# 5_GPIOBanks.net
KiCad netlist of a schematic drawn in Altium Designer
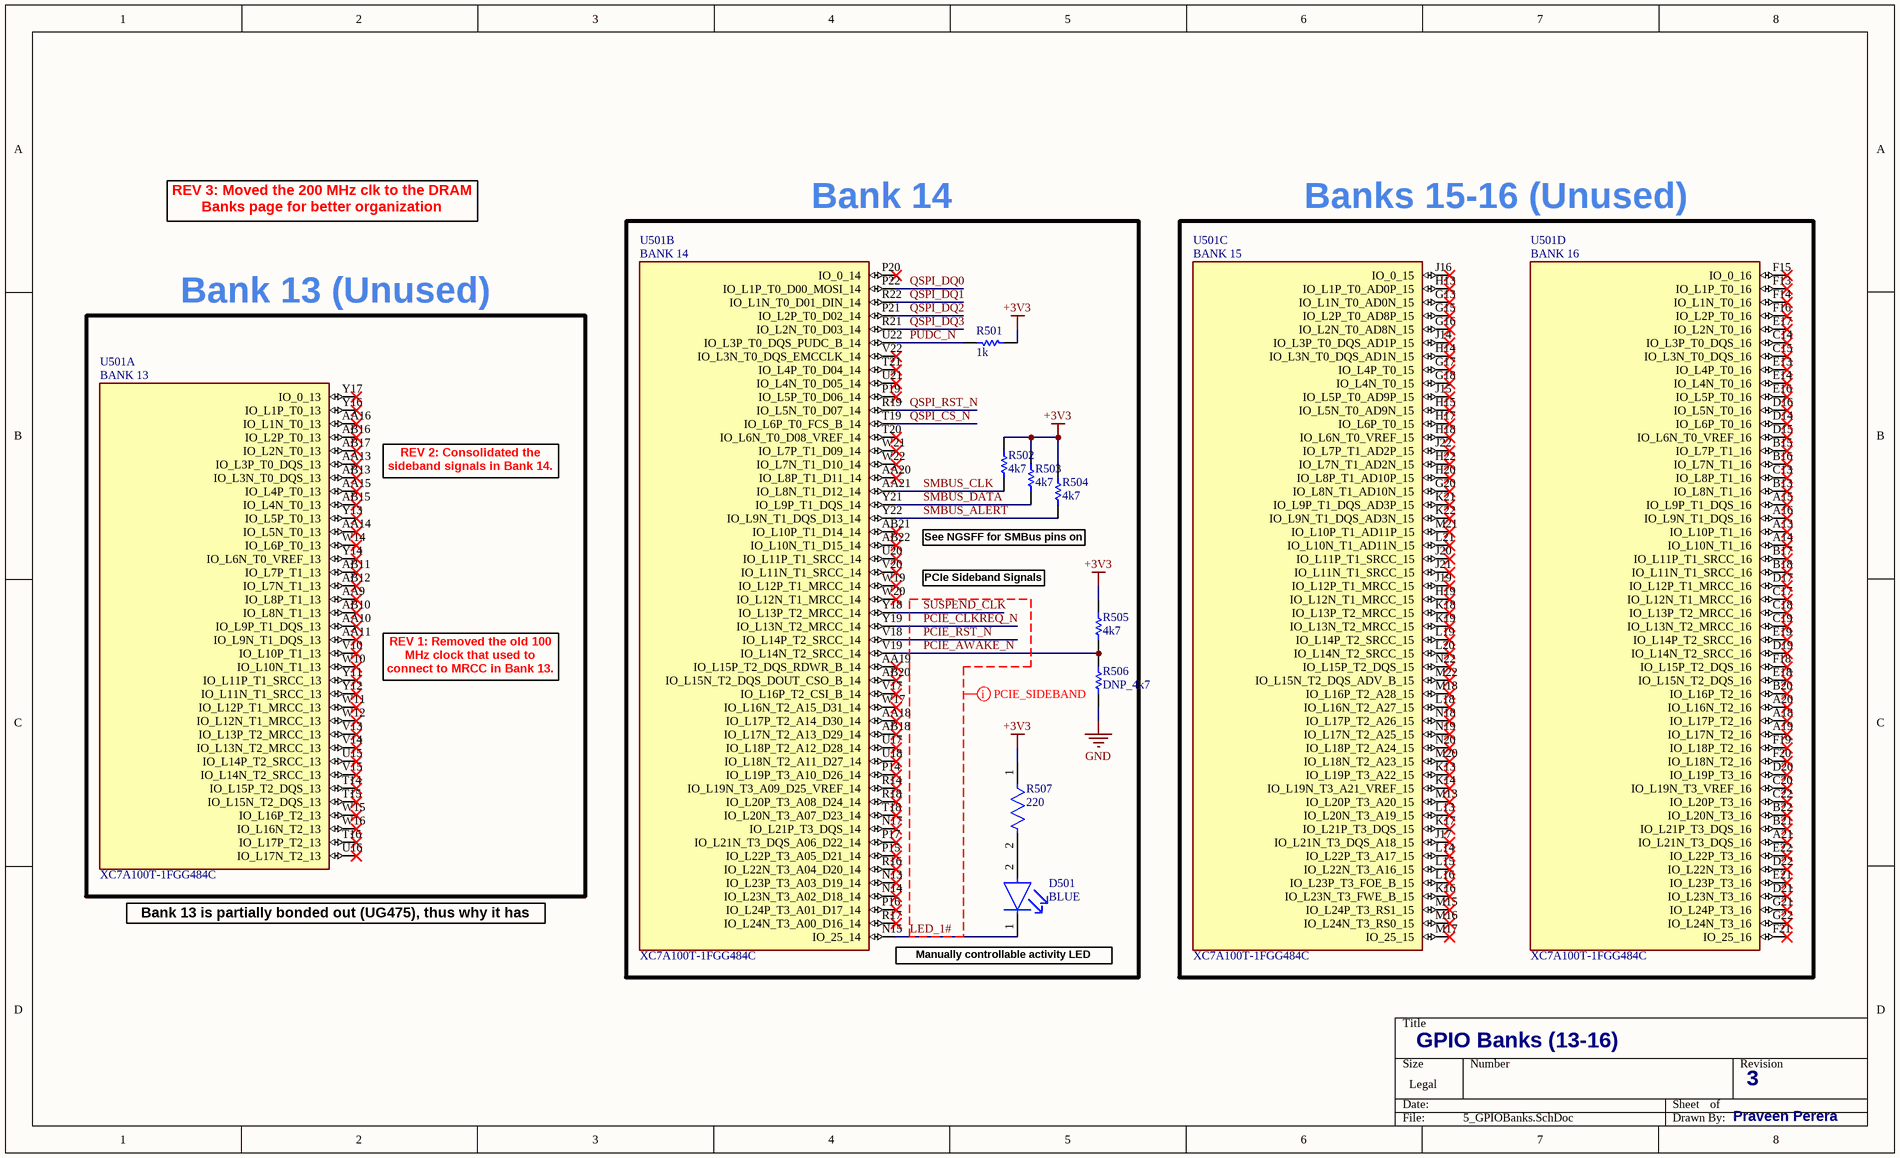
[diagram p0: 5_GPIOBanks.SchDoc]

(export (version "E")
  (design (tool "Eeschema 10.0.6"))
  (components
    (comp (ref "D501")
      (value "BLUE")
      (footprint "FP-LTST-C193TBKT-5A-MFG")
      (description "LTST-C193TBKT-5A\r\n\r\nLED BLUE CLEAR CHIP SMD")
      (libsource (lib "Altium Content Vault") (part "8706943c75ba83719d021d2fdc84c58"))
    )
    (comp (ref "R501")
      (value "1k")
      (footprint "RESC0603X28X15ML05T05")
      (description "CRCW02011K00JNED")
      (fields (field (name "MANUFACTURER") "Vishay Dale"))
      (libsource (lib "Altium Content Vault") (part "RES"))
    )
    (comp (ref "R502")
      (value "4k7")
      (footprint "RESC0603X28X15NL05T05")
      (description "CRCW02014K70FNED")
      (fields (field (name "MANUFACTURER") "Vishay Dale"))
      (libsource (lib "Altium Content Vault") (part "RES"))
    )
    (comp (ref "R503")
      (value "4k7")
      (footprint "RESC0603X28X15NL05T05")
      (description "CRCW02014K70FNED")
      (fields (field (name "MANUFACTURER") "Vishay Dale"))
      (libsource (lib "Altium Content Vault") (part "RES"))
    )
    (comp (ref "R504")
      (value "4k7")
      (footprint "RESC0603X28X15NL05T05")
      (description "CRCW02014K70FNED")
      (fields (field (name "MANUFACTURER") "Vishay Dale"))
      (libsource (lib "Altium Content Vault") (part "RES"))
    )
    (comp (ref "R505")
      (value "4k7")
      (footprint "RESC0603X28X15NL05T05")
      (description "CRCW02014K70FNED")
      (fields (field (name "MANUFACTURER") "Vishay Dale"))
      (libsource (lib "Altium Content Vault") (part "RES"))
    )
    (comp (ref "R506")
      (value "DNP_4k7")
      (footprint "RESC0603X28X15NL05T05")
      (description "CRCW02014K70FNED")
      (fields (field (name "MANUFACTURER") "Vishay Dale"))
      (libsource (lib "Altium Content Vault") (part "RES"))
    )
    (comp (ref "R507")
      (value "220")
      (footprint "FP-CR0402-IPC_B")
      (description "CR0402-FX-2200GLF\r\n\r\nThick Film Chip Resistors 0402 220Ω 0.0625W 1% 100ppm/°C")
      (fields (field (name "TOLERANCE") "1%"))
      (libsource (lib "Altium Content Vault") (part "1029c3af85768c4190bb7ad29bc67b5"))
    )
    (comp (ref "U501")
      (value "XC7A100T-1FGG484C")
      (footprint "BGA484C100P22X22_2300X2300X260N")
      (description "Artix-7 Field Programmable Gate Array (FPGA) IC 285 4976640 101440 484-BBGA")
      (fields (field (name "MF") "Xilinx Inc."))
      (libsource (lib "XC7A100T-1FGG484C - Modified") (part "XC7A100T-1FGG484C"))
    )
  )
  (nets
    (net (code "1") (name "+3V3") (class "Default")
      (node (ref "R501") (pin "1") (pinfunction "1_1") (pintype "passive"))
      (node (ref "R502") (pin "2") (pinfunction "2_2") (pintype "passive"))
      (node (ref "R503") (pin "2") (pinfunction "2_2") (pintype "passive"))
      (node (ref "R504") (pin "2") (pinfunction "2_2") (pintype "passive"))
      (node (ref "R505") (pin "2") (pinfunction "2_2") (pintype "passive"))
      (node (ref "R507") (pin "1") (pinfunction "1_1") (pintype "passive"))
    )
    (net (code "2") (name "/LED_1#") (class "Default")
      (node (ref "D501") (pin "1") (pinfunction "C_1") (pintype "passive"))
      (node (ref "U501") (pin "N15") (pinfunction "IO_25_14_N15") (pintype "bidirectional"))
    )
    (net (code "3") (name "/PCIE_AWAKE_N") (class "Default")
      (node (ref "R505") (pin "1") (pinfunction "1_1") (pintype "passive"))
      (node (ref "R506") (pin "2") (pinfunction "2_2") (pintype "passive"))
      (node (ref "U501") (pin "V19") (pinfunction "IO_L14N_T2_SRCC_14_V19") (pintype "bidirectional"))
    )
    (net (code "4") (name "/PCIE_CLKREQ_N") (class "Default")
      (node (ref "U501") (pin "Y19") (pinfunction "IO_L13N_T2_MRCC_14_Y19") (pintype "bidirectional"))
    )
    (net (code "5") (name "/PCIE_RST_N") (class "Default")
      (node (ref "U501") (pin "V18") (pinfunction "IO_L14P_T2_SRCC_14_V18") (pintype "bidirectional"))
    )
    (net (code "6") (name "/PUDC_N") (class "Default")
      (node (ref "R501") (pin "2") (pinfunction "2_2") (pintype "passive"))
      (node (ref "U501") (pin "U22") (pinfunction "IO_L3P_T0_DQS_PUDC_B_14_U22") (pintype "bidirectional"))
    )
    (net (code "7") (name "/QSPI_CS_N") (class "Default")
      (node (ref "U501") (pin "T19") (pinfunction "IO_L6P_T0_FCS_B_14_T19") (pintype "bidirectional"))
    )
    (net (code "8") (name "/QSPI_DQ0") (class "Default")
      (node (ref "U501") (pin "P22") (pinfunction "IO_L1P_T0_D00_MOSI_14_P22") (pintype "bidirectional"))
    )
    (net (code "9") (name "/QSPI_DQ1") (class "Default")
      (node (ref "U501") (pin "R22") (pinfunction "IO_L1N_T0_D01_DIN_14_R22") (pintype "bidirectional"))
    )
    (net (code "10") (name "/QSPI_DQ2") (class "Default")
      (node (ref "U501") (pin "P21") (pinfunction "IO_L2P_T0_D02_14_P21") (pintype "bidirectional"))
    )
    (net (code "11") (name "/QSPI_DQ3") (class "Default")
      (node (ref "U501") (pin "R21") (pinfunction "IO_L2N_T0_D03_14_R21") (pintype "bidirectional"))
    )
    (net (code "12") (name "/QSPI_RST_N") (class "Default")
      (node (ref "U501") (pin "R19") (pinfunction "IO_L5N_T0_D07_14_R19") (pintype "bidirectional"))
    )
    (net (code "13") (name "/SMBUS_ALERT") (class "Default")
      (node (ref "R504") (pin "1") (pinfunction "1_1") (pintype "passive"))
      (node (ref "U501") (pin "Y22") (pinfunction "IO_L9N_T1_DQS_D13_14_Y22") (pintype "bidirectional"))
    )
    (net (code "14") (name "/SMBUS_CLK") (class "Default")
      (node (ref "R502") (pin "1") (pinfunction "1_1") (pintype "passive"))
      (node (ref "U501") (pin "AA21") (pinfunction "IO_L8N_T1_D12_14_AA21") (pintype "bidirectional"))
    )
    (net (code "15") (name "/SMBUS_DATA") (class "Default")
      (node (ref "R503") (pin "1") (pinfunction "1_1") (pintype "passive"))
      (node (ref "U501") (pin "Y21") (pinfunction "IO_L9P_T1_DQS_14_Y21") (pintype "bidirectional"))
    )
    (net (code "16") (name "/SUSPEND_CLK") (class "Default")
      (node (ref "U501") (pin "Y18") (pinfunction "IO_L13P_T2_MRCC_14_Y18") (pintype "bidirectional"))
    )
    (net (code "17") (name "GND") (class "Default")
      (node (ref "R506") (pin "1") (pinfunction "1_1") (pintype "passive"))
    )
    (net (code "18") (name "Net-(D501-A)") (class "Default")
      (node (ref "D501") (pin "2") (pinfunction "A_2") (pintype "passive"))
      (node (ref "R507") (pin "2") (pinfunction "2_2") (pintype "passive"))
    )
    (net (code "19") (name "unconnected-(U501A-IO_0_13-PadY17)") (class "Default")
      (node (ref "U501") (pin "Y17") (pinfunction "IO_0_13_Y17") (pintype "bidirectional+no_connect"))
    )
    (net (code "20") (name "unconnected-(U501A-IO_L1N_T0_13-PadAA16)") (class "Default")
      (node (ref "U501") (pin "AA16") (pinfunction "IO_L1N_T0_13_AA16") (pintype "bidirectional+no_connect"))
    )
    (net (code "21") (name "unconnected-(U501A-IO_L1P_T0_13-PadY16)") (class "Default")
      (node (ref "U501") (pin "Y16") (pinfunction "IO_L1P_T0_13_Y16") (pintype "bidirectional+no_connect"))
    )
    (net (code "22") (name "unconnected-(U501A-IO_L2N_T0_13-PadAB17)") (class "Default")
      (node (ref "U501") (pin "AB17") (pinfunction "IO_L2N_T0_13_AB17") (pintype "bidirectional+no_connect"))
    )
    (net (code "23") (name "unconnected-(U501A-IO_L2P_T0_13-PadAB16)") (class "Default")
      (node (ref "U501") (pin "AB16") (pinfunction "IO_L2P_T0_13_AB16") (pintype "bidirectional+no_connect"))
    )
    (net (code "24") (name "unconnected-(U501A-IO_L3N_T0_DQS_13-PadAB13)") (class "Default")
      (node (ref "U501") (pin "AB13") (pinfunction "IO_L3N_T0_DQS_13_AB13") (pintype "bidirectional+no_connect"))
    )
    (net (code "25") (name "unconnected-(U501A-IO_L3P_T0_DQS_13-PadAA13)") (class "Default")
      (node (ref "U501") (pin "AA13") (pinfunction "IO_L3P_T0_DQS_13_AA13") (pintype "bidirectional+no_connect"))
    )
    (net (code "26") (name "unconnected-(U501A-IO_L4N_T0_13-PadAB15)") (class "Default")
      (node (ref "U501") (pin "AB15") (pinfunction "IO_L4N_T0_13_AB15") (pintype "bidirectional+no_connect"))
    )
    (net (code "27") (name "unconnected-(U501A-IO_L4P_T0_13-PadAA15)") (class "Default")
      (node (ref "U501") (pin "AA15") (pinfunction "IO_L4P_T0_13_AA15") (pintype "bidirectional+no_connect"))
    )
    (net (code "28") (name "unconnected-(U501A-IO_L5N_T0_13-PadAA14)") (class "Default")
      (node (ref "U501") (pin "AA14") (pinfunction "IO_L5N_T0_13_AA14") (pintype "bidirectional+no_connect"))
    )
    (net (code "29") (name "unconnected-(U501A-IO_L5P_T0_13-PadY13)") (class "Default")
      (node (ref "U501") (pin "Y13") (pinfunction "IO_L5P_T0_13_Y13") (pintype "bidirectional+no_connect"))
    )
    (net (code "30") (name "unconnected-(U501A-IO_L6N_T0_VREF_13-PadY14)") (class "Default")
      (node (ref "U501") (pin "Y14") (pinfunction "IO_L6N_T0_VREF_13_Y14") (pintype "bidirectional+no_connect"))
    )
    (net (code "31") (name "unconnected-(U501A-IO_L6P_T0_13-PadW14)") (class "Default")
      (node (ref "U501") (pin "W14") (pinfunction "IO_L6P_T0_13_W14") (pintype "bidirectional+no_connect"))
    )
    (net (code "32") (name "unconnected-(U501A-IO_L7N_T1_13-PadAB12)") (class "Default")
      (node (ref "U501") (pin "AB12") (pinfunction "IO_L7N_T1_13_AB12") (pintype "bidirectional+no_connect"))
    )
    (net (code "33") (name "unconnected-(U501A-IO_L7P_T1_13-PadAB11)") (class "Default")
      (node (ref "U501") (pin "AB11") (pinfunction "IO_L7P_T1_13_AB11") (pintype "bidirectional+no_connect"))
    )
    (net (code "34") (name "unconnected-(U501A-IO_L8N_T1_13-PadAB10)") (class "Default")
      (node (ref "U501") (pin "AB10") (pinfunction "IO_L8N_T1_13_AB10") (pintype "bidirectional+no_connect"))
    )
    (net (code "35") (name "unconnected-(U501A-IO_L8P_T1_13-PadAA9)") (class "Default")
      (node (ref "U501") (pin "AA9") (pinfunction "IO_L8P_T1_13_AA9") (pintype "bidirectional+no_connect"))
    )
    (net (code "36") (name "unconnected-(U501A-IO_L9N_T1_DQS_13-PadAA11)") (class "Default")
      (node (ref "U501") (pin "AA11") (pinfunction "IO_L9N_T1_DQS_13_AA11") (pintype "bidirectional+no_connect"))
    )
    (net (code "37") (name "unconnected-(U501A-IO_L9P_T1_DQS_13-PadAA10)") (class "Default")
      (node (ref "U501") (pin "AA10") (pinfunction "IO_L9P_T1_DQS_13_AA10") (pintype "bidirectional+no_connect"))
    )
    (net (code "38") (name "unconnected-(U501A-IO_L10N_T1_13-PadW10)") (class "Default")
      (node (ref "U501") (pin "W10") (pinfunction "IO_L10N_T1_13_W10") (pintype "bidirectional+no_connect"))
    )
    (net (code "39") (name "unconnected-(U501A-IO_L10P_T1_13-PadV10)") (class "Default")
      (node (ref "U501") (pin "V10") (pinfunction "IO_L10P_T1_13_V10") (pintype "bidirectional+no_connect"))
    )
    (net (code "40") (name "unconnected-(U501A-IO_L11N_T1_SRCC_13-PadY12)") (class "Default")
      (node (ref "U501") (pin "Y12") (pinfunction "IO_L11N_T1_SRCC_13_Y12") (pintype "bidirectional+no_connect"))
    )
    (net (code "41") (name "unconnected-(U501A-IO_L11P_T1_SRCC_13-PadY11)") (class "Default")
      (node (ref "U501") (pin "Y11") (pinfunction "IO_L11P_T1_SRCC_13_Y11") (pintype "bidirectional+no_connect"))
    )
    (net (code "42") (name "unconnected-(U501A-IO_L12N_T1_MRCC_13-PadW12)") (class "Default")
      (node (ref "U501") (pin "W12") (pinfunction "IO_L12N_T1_MRCC_13_W12") (pintype "bidirectional+no_connect"))
    )
    (net (code "43") (name "unconnected-(U501A-IO_L12P_T1_MRCC_13-PadW11)") (class "Default")
      (node (ref "U501") (pin "W11") (pinfunction "IO_L12P_T1_MRCC_13_W11") (pintype "bidirectional+no_connect"))
    )
    (net (code "44") (name "unconnected-(U501A-IO_L13N_T2_MRCC_13-PadV14)") (class "Default")
      (node (ref "U501") (pin "V14") (pinfunction "IO_L13N_T2_MRCC_13_V14") (pintype "bidirectional+no_connect"))
    )
    (net (code "45") (name "unconnected-(U501A-IO_L13P_T2_MRCC_13-PadV13)") (class "Default")
      (node (ref "U501") (pin "V13") (pinfunction "IO_L13P_T2_MRCC_13_V13") (pintype "bidirectional+no_connect"))
    )
    (net (code "46") (name "unconnected-(U501A-IO_L14N_T2_SRCC_13-PadV15)") (class "Default")
      (node (ref "U501") (pin "V15") (pinfunction "IO_L14N_T2_SRCC_13_V15") (pintype "bidirectional+no_connect"))
    )
    (net (code "47") (name "unconnected-(U501A-IO_L14P_T2_SRCC_13-PadU15)") (class "Default")
      (node (ref "U501") (pin "U15") (pinfunction "IO_L14P_T2_SRCC_13_U15") (pintype "bidirectional+no_connect"))
    )
    (net (code "48") (name "unconnected-(U501A-IO_L15N_T2_DQS_13-PadT15)") (class "Default")
      (node (ref "U501") (pin "T15") (pinfunction "IO_L15N_T2_DQS_13_T15") (pintype "bidirectional+no_connect"))
    )
    (net (code "49") (name "unconnected-(U501A-IO_L15P_T2_DQS_13-PadT14)") (class "Default")
      (node (ref "U501") (pin "T14") (pinfunction "IO_L15P_T2_DQS_13_T14") (pintype "bidirectional+no_connect"))
    )
    (net (code "50") (name "unconnected-(U501A-IO_L16N_T2_13-PadW16)") (class "Default")
      (node (ref "U501") (pin "W16") (pinfunction "IO_L16N_T2_13_W16") (pintype "bidirectional+no_connect"))
    )
    (net (code "51") (name "unconnected-(U501A-IO_L16P_T2_13-PadW15)") (class "Default")
      (node (ref "U501") (pin "W15") (pinfunction "IO_L16P_T2_13_W15") (pintype "bidirectional+no_connect"))
    )
    (net (code "52") (name "unconnected-(U501A-IO_L17N_T2_13-PadU16)") (class "Default")
      (node (ref "U501") (pin "U16") (pinfunction "IO_L17N_T2_13_U16") (pintype "bidirectional+no_connect"))
    )
    (net (code "53") (name "unconnected-(U501A-IO_L17P_T2_13-PadT16)") (class "Default")
      (node (ref "U501") (pin "T16") (pinfunction "IO_L17P_T2_13_T16") (pintype "bidirectional+no_connect"))
    )
    (net (code "54") (name "unconnected-(U501B-IO_0_14-PadP20)") (class "Default")
      (node (ref "U501") (pin "P20") (pinfunction "IO_0_14_P20") (pintype "bidirectional+no_connect"))
    )
    (net (code "55") (name "unconnected-(U501B-IO_L3N_T0_DQS_EMCCLK_14-PadV22)") (class "Default")
      (node (ref "U501") (pin "V22") (pinfunction "IO_L3N_T0_DQS_EMCCLK_14_V22") (pintype "bidirectional+no_connect"))
    )
    (net (code "56") (name "unconnected-(U501B-IO_L4N_T0_D05_14-PadU21)") (class "Default")
      (node (ref "U501") (pin "U21") (pinfunction "IO_L4N_T0_D05_14_U21") (pintype "bidirectional+no_connect"))
    )
    (net (code "57") (name "unconnected-(U501B-IO_L4P_T0_D04_14-PadT21)") (class "Default")
      (node (ref "U501") (pin "T21") (pinfunction "IO_L4P_T0_D04_14_T21") (pintype "bidirectional+no_connect"))
    )
    (net (code "58") (name "unconnected-(U501B-IO_L5P_T0_D06_14-PadP19)") (class "Default")
      (node (ref "U501") (pin "P19") (pinfunction "IO_L5P_T0_D06_14_P19") (pintype "bidirectional+no_connect"))
    )
    (net (code "59") (name "unconnected-(U501B-IO_L6N_T0_D08_VREF_14-PadT20)") (class "Default")
      (node (ref "U501") (pin "T20") (pinfunction "IO_L6N_T0_D08_VREF_14_T20") (pintype "bidirectional+no_connect"))
    )
    (net (code "60") (name "unconnected-(U501B-IO_L7N_T1_D10_14-PadW22)") (class "Default")
      (node (ref "U501") (pin "W22") (pinfunction "IO_L7N_T1_D10_14_W22") (pintype "bidirectional+no_connect"))
    )
    (net (code "61") (name "unconnected-(U501B-IO_L7P_T1_D09_14-PadW21)") (class "Default")
      (node (ref "U501") (pin "W21") (pinfunction "IO_L7P_T1_D09_14_W21") (pintype "bidirectional+no_connect"))
    )
    (net (code "62") (name "unconnected-(U501B-IO_L8P_T1_D11_14-PadAA20)") (class "Default")
      (node (ref "U501") (pin "AA20") (pinfunction "IO_L8P_T1_D11_14_AA20") (pintype "bidirectional+no_connect"))
    )
    (net (code "63") (name "unconnected-(U501B-IO_L10N_T1_D15_14-PadAB22)") (class "Default")
      (node (ref "U501") (pin "AB22") (pinfunction "IO_L10N_T1_D15_14_AB22") (pintype "bidirectional+no_connect"))
    )
    (net (code "64") (name "unconnected-(U501B-IO_L10P_T1_D14_14-PadAB21)") (class "Default")
      (node (ref "U501") (pin "AB21") (pinfunction "IO_L10P_T1_D14_14_AB21") (pintype "bidirectional+no_connect"))
    )
    (net (code "65") (name "unconnected-(U501B-IO_L11N_T1_SRCC_14-PadV20)") (class "Default")
      (node (ref "U501") (pin "V20") (pinfunction "IO_L11N_T1_SRCC_14_V20") (pintype "bidirectional+no_connect"))
    )
    (net (code "66") (name "unconnected-(U501B-IO_L11P_T1_SRCC_14-PadU20)") (class "Default")
      (node (ref "U501") (pin "U20") (pinfunction "IO_L11P_T1_SRCC_14_U20") (pintype "bidirectional+no_connect"))
    )
    (net (code "67") (name "unconnected-(U501B-IO_L12N_T1_MRCC_14-PadW20)") (class "Default")
      (node (ref "U501") (pin "W20") (pinfunction "IO_L12N_T1_MRCC_14_W20") (pintype "bidirectional+no_connect"))
    )
    (net (code "68") (name "unconnected-(U501B-IO_L12P_T1_MRCC_14-PadW19)") (class "Default")
      (node (ref "U501") (pin "W19") (pinfunction "IO_L12P_T1_MRCC_14_W19") (pintype "bidirectional+no_connect"))
    )
    (net (code "69") (name "unconnected-(U501B-IO_L15N_T2_DQS_DOUT_CSO_B_14-PadAB20)") (class "Default")
      (node (ref "U501") (pin "AB20") (pinfunction "IO_L15N_T2_DQS_DOUT_CSO_B_14_AB20") (pintype "bidirectional+no_connect"))
    )
    (net (code "70") (name "unconnected-(U501B-IO_L15P_T2_DQS_RDWR_B_14-PadAA19)") (class "Default")
      (node (ref "U501") (pin "AA19") (pinfunction "IO_L15P_T2_DQS_RDWR_B_14_AA19") (pintype "bidirectional+no_connect"))
    )
    (net (code "71") (name "unconnected-(U501B-IO_L16N_T2_A15_D31_14-PadW17)") (class "Default")
      (node (ref "U501") (pin "W17") (pinfunction "IO_L16N_T2_A15_D31_14_W17") (pintype "bidirectional+no_connect"))
    )
    (net (code "72") (name "unconnected-(U501B-IO_L16P_T2_CSI_B_14-PadV17)") (class "Default")
      (node (ref "U501") (pin "V17") (pinfunction "IO_L16P_T2_CSI_B_14_V17") (pintype "bidirectional+no_connect"))
    )
    (net (code "73") (name "unconnected-(U501B-IO_L17N_T2_A13_D29_14-PadAB18)") (class "Default")
      (node (ref "U501") (pin "AB18") (pinfunction "IO_L17N_T2_A13_D29_14_AB18") (pintype "bidirectional+no_connect"))
    )
    (net (code "74") (name "unconnected-(U501B-IO_L17P_T2_A14_D30_14-PadAA18)") (class "Default")
      (node (ref "U501") (pin "AA18") (pinfunction "IO_L17P_T2_A14_D30_14_AA18") (pintype "bidirectional+no_connect"))
    )
    (net (code "75") (name "unconnected-(U501B-IO_L18N_T2_A11_D27_14-PadU18)") (class "Default")
      (node (ref "U501") (pin "U18") (pinfunction "IO_L18N_T2_A11_D27_14_U18") (pintype "bidirectional+no_connect"))
    )
    (net (code "76") (name "unconnected-(U501B-IO_L18P_T2_A12_D28_14-PadU17)") (class "Default")
      (node (ref "U501") (pin "U17") (pinfunction "IO_L18P_T2_A12_D28_14_U17") (pintype "bidirectional+no_connect"))
    )
    (net (code "77") (name "unconnected-(U501B-IO_L19N_T3_A09_D25_VREF_14-PadR14)") (class "Default")
      (node (ref "U501") (pin "R14") (pinfunction "IO_L19N_T3_A09_D25_VREF_14_R14") (pintype "bidirectional+no_connect"))
    )
    (net (code "78") (name "unconnected-(U501B-IO_L19P_T3_A10_D26_14-PadP14)") (class "Default")
      (node (ref "U501") (pin "P14") (pinfunction "IO_L19P_T3_A10_D26_14_P14") (pintype "bidirectional+no_connect"))
    )
    (net (code "79") (name "unconnected-(U501B-IO_L20N_T3_A07_D23_14-PadT18)") (class "Default")
      (node (ref "U501") (pin "T18") (pinfunction "IO_L20N_T3_A07_D23_14_T18") (pintype "bidirectional+no_connect"))
    )
    (net (code "80") (name "unconnected-(U501B-IO_L20P_T3_A08_D24_14-PadR18)") (class "Default")
      (node (ref "U501") (pin "R18") (pinfunction "IO_L20P_T3_A08_D24_14_R18") (pintype "bidirectional+no_connect"))
    )
    (net (code "81") (name "unconnected-(U501B-IO_L21N_T3_DQS_A06_D22_14-PadP17)") (class "Default")
      (node (ref "U501") (pin "P17") (pinfunction "IO_L21N_T3_DQS_A06_D22_14_P17") (pintype "bidirectional+no_connect"))
    )
    (net (code "82") (name "unconnected-(U501B-IO_L21P_T3_DQS_14-PadN17)") (class "Default")
      (node (ref "U501") (pin "N17") (pinfunction "IO_L21P_T3_DQS_14_N17") (pintype "bidirectional+no_connect"))
    )
    (net (code "83") (name "unconnected-(U501B-IO_L22N_T3_A04_D20_14-PadR16)") (class "Default")
      (node (ref "U501") (pin "R16") (pinfunction "IO_L22N_T3_A04_D20_14_R16") (pintype "bidirectional+no_connect"))
    )
    (net (code "84") (name "unconnected-(U501B-IO_L22P_T3_A05_D21_14-PadP15)") (class "Default")
      (node (ref "U501") (pin "P15") (pinfunction "IO_L22P_T3_A05_D21_14_P15") (pintype "bidirectional+no_connect"))
    )
    (net (code "85") (name "unconnected-(U501B-IO_L23N_T3_A02_D18_14-PadN14)") (class "Default")
      (node (ref "U501") (pin "N14") (pinfunction "IO_L23N_T3_A02_D18_14_N14") (pintype "bidirectional+no_connect"))
    )
    (net (code "86") (name "unconnected-(U501B-IO_L23P_T3_A03_D19_14-PadN13)") (class "Default")
      (node (ref "U501") (pin "N13") (pinfunction "IO_L23P_T3_A03_D19_14_N13") (pintype "bidirectional+no_connect"))
    )
    (net (code "87") (name "unconnected-(U501B-IO_L24N_T3_A00_D16_14-PadR17)") (class "Default")
      (node (ref "U501") (pin "R17") (pinfunction "IO_L24N_T3_A00_D16_14_R17") (pintype "bidirectional+no_connect"))
    )
    (net (code "88") (name "unconnected-(U501B-IO_L24P_T3_A01_D17_14-PadP16)") (class "Default")
      (node (ref "U501") (pin "P16") (pinfunction "IO_L24P_T3_A01_D17_14_P16") (pintype "bidirectional+no_connect"))
    )
    (net (code "89") (name "unconnected-(U501C-IO_0_15-PadJ16)") (class "Default")
      (node (ref "U501") (pin "J16") (pinfunction "IO_0_15_J16") (pintype "bidirectional+no_connect"))
    )
    (net (code "90") (name "unconnected-(U501C-IO_25_15-PadM17)") (class "Default")
      (node (ref "U501") (pin "M17") (pinfunction "IO_25_15_M17") (pintype "bidirectional+no_connect"))
    )
    (net (code "91") (name "unconnected-(U501C-IO_L1N_T0_AD0N_15-PadG13)") (class "Default")
      (node (ref "U501") (pin "G13") (pinfunction "IO_L1N_T0_AD0N_15_G13") (pintype "bidirectional+no_connect"))
    )
    (net (code "92") (name "unconnected-(U501C-IO_L1P_T0_AD0P_15-PadH13)") (class "Default")
      (node (ref "U501") (pin "H13") (pinfunction "IO_L1P_T0_AD0P_15_H13") (pintype "bidirectional+no_connect"))
    )
    (net (code "93") (name "unconnected-(U501C-IO_L2N_T0_AD8N_15-PadG16)") (class "Default")
      (node (ref "U501") (pin "G16") (pinfunction "IO_L2N_T0_AD8N_15_G16") (pintype "bidirectional+no_connect"))
    )
    (net (code "94") (name "unconnected-(U501C-IO_L2P_T0_AD8P_15-PadG15)") (class "Default")
      (node (ref "U501") (pin "G15") (pinfunction "IO_L2P_T0_AD8P_15_G15") (pintype "bidirectional+no_connect"))
    )
    (net (code "95") (name "unconnected-(U501C-IO_L3N_T0_DQS_AD1N_15-PadH14)") (class "Default")
      (node (ref "U501") (pin "H14") (pinfunction "IO_L3N_T0_DQS_AD1N_15_H14") (pintype "bidirectional+no_connect"))
    )
    (net (code "96") (name "unconnected-(U501C-IO_L3P_T0_DQS_AD1P_15-PadJ14)") (class "Default")
      (node (ref "U501") (pin "J14") (pinfunction "IO_L3P_T0_DQS_AD1P_15_J14") (pintype "bidirectional+no_connect"))
    )
    (net (code "97") (name "unconnected-(U501C-IO_L4N_T0_15-PadG18)") (class "Default")
      (node (ref "U501") (pin "G18") (pinfunction "IO_L4N_T0_15_G18") (pintype "bidirectional+no_connect"))
    )
    (net (code "98") (name "unconnected-(U501C-IO_L4P_T0_15-PadG17)") (class "Default")
      (node (ref "U501") (pin "G17") (pinfunction "IO_L4P_T0_15_G17") (pintype "bidirectional+no_connect"))
    )
    (net (code "99") (name "unconnected-(U501C-IO_L5N_T0_AD9N_15-PadH15)") (class "Default")
      (node (ref "U501") (pin "H15") (pinfunction "IO_L5N_T0_AD9N_15_H15") (pintype "bidirectional+no_connect"))
    )
    (net (code "100") (name "unconnected-(U501C-IO_L5P_T0_AD9P_15-PadJ15)") (class "Default")
      (node (ref "U501") (pin "J15") (pinfunction "IO_L5P_T0_AD9P_15_J15") (pintype "bidirectional+no_connect"))
    )
    (net (code "101") (name "unconnected-(U501C-IO_L6N_T0_VREF_15-PadH18)") (class "Default")
      (node (ref "U501") (pin "H18") (pinfunction "IO_L6N_T0_VREF_15_H18") (pintype "bidirectional+no_connect"))
    )
    (net (code "102") (name "unconnected-(U501C-IO_L6P_T0_15-PadH17)") (class "Default")
      (node (ref "U501") (pin "H17") (pinfunction "IO_L6P_T0_15_H17") (pintype "bidirectional+no_connect"))
    )
    (net (code "103") (name "unconnected-(U501C-IO_L7N_T1_AD2N_15-PadH22)") (class "Default")
      (node (ref "U501") (pin "H22") (pinfunction "IO_L7N_T1_AD2N_15_H22") (pintype "bidirectional+no_connect"))
    )
    (net (code "104") (name "unconnected-(U501C-IO_L7P_T1_AD2P_15-PadJ22)") (class "Default")
      (node (ref "U501") (pin "J22") (pinfunction "IO_L7P_T1_AD2P_15_J22") (pintype "bidirectional+no_connect"))
    )
    (net (code "105") (name "unconnected-(U501C-IO_L8N_T1_AD10N_15-PadG20)") (class "Default")
      (node (ref "U501") (pin "G20") (pinfunction "IO_L8N_T1_AD10N_15_G20") (pintype "bidirectional+no_connect"))
    )
    (net (code "106") (name "unconnected-(U501C-IO_L8P_T1_AD10P_15-PadH20)") (class "Default")
      (node (ref "U501") (pin "H20") (pinfunction "IO_L8P_T1_AD10P_15_H20") (pintype "bidirectional+no_connect"))
    )
    (net (code "107") (name "unconnected-(U501C-IO_L9N_T1_DQS_AD3N_15-PadK22)") (class "Default")
      (node (ref "U501") (pin "K22") (pinfunction "IO_L9N_T1_DQS_AD3N_15_K22") (pintype "bidirectional+no_connect"))
    )
    (net (code "108") (name "unconnected-(U501C-IO_L9P_T1_DQS_AD3P_15-PadK21)") (class "Default")
      (node (ref "U501") (pin "K21") (pinfunction "IO_L9P_T1_DQS_AD3P_15_K21") (pintype "bidirectional+no_connect"))
    )
    (net (code "109") (name "unconnected-(U501C-IO_L10N_T1_AD11N_15-PadL21)") (class "Default")
      (node (ref "U501") (pin "L21") (pinfunction "IO_L10N_T1_AD11N_15_L21") (pintype "bidirectional+no_connect"))
    )
    (net (code "110") (name "unconnected-(U501C-IO_L10P_T1_AD11P_15-PadM21)") (class "Default")
      (node (ref "U501") (pin "M21") (pinfunction "IO_L10P_T1_AD11P_15_M21") (pintype "bidirectional+no_connect"))
    )
    (net (code "111") (name "unconnected-(U501C-IO_L11N_T1_SRCC_15-PadJ21)") (class "Default")
      (node (ref "U501") (pin "J21") (pinfunction "IO_L11N_T1_SRCC_15_J21") (pintype "bidirectional+no_connect"))
    )
    (net (code "112") (name "unconnected-(U501C-IO_L11P_T1_SRCC_15-PadJ20)") (class "Default")
      (node (ref "U501") (pin "J20") (pinfunction "IO_L11P_T1_SRCC_15_J20") (pintype "bidirectional+no_connect"))
    )
    (net (code "113") (name "unconnected-(U501C-IO_L12N_T1_MRCC_15-PadH19)") (class "Default")
      (node (ref "U501") (pin "H19") (pinfunction "IO_L12N_T1_MRCC_15_H19") (pintype "bidirectional+no_connect"))
    )
    (net (code "114") (name "unconnected-(U501C-IO_L12P_T1_MRCC_15-PadJ19)") (class "Default")
      (node (ref "U501") (pin "J19") (pinfunction "IO_L12P_T1_MRCC_15_J19") (pintype "bidirectional+no_connect"))
    )
    (net (code "115") (name "unconnected-(U501C-IO_L13N_T2_MRCC_15-PadK19)") (class "Default")
      (node (ref "U501") (pin "K19") (pinfunction "IO_L13N_T2_MRCC_15_K19") (pintype "bidirectional+no_connect"))
    )
    (net (code "116") (name "unconnected-(U501C-IO_L13P_T2_MRCC_15-PadK18)") (class "Default")
      (node (ref "U501") (pin "K18") (pinfunction "IO_L13P_T2_MRCC_15_K18") (pintype "bidirectional+no_connect"))
    )
    (net (code "117") (name "unconnected-(U501C-IO_L14N_T2_SRCC_15-PadL20)") (class "Default")
      (node (ref "U501") (pin "L20") (pinfunction "IO_L14N_T2_SRCC_15_L20") (pintype "bidirectional+no_connect"))
    )
    (net (code "118") (name "unconnected-(U501C-IO_L14P_T2_SRCC_15-PadL19)") (class "Default")
      (node (ref "U501") (pin "L19") (pinfunction "IO_L14P_T2_SRCC_15_L19") (pintype "bidirectional+no_connect"))
    )
    (net (code "119") (name "unconnected-(U501C-IO_L15N_T2_DQS_ADV_B_15-PadM22)") (class "Default")
      (node (ref "U501") (pin "M22") (pinfunction "IO_L15N_T2_DQS_ADV_B_15_M22") (pintype "bidirectional+no_connect"))
    )
    (net (code "120") (name "unconnected-(U501C-IO_L15P_T2_DQS_15-PadN22)") (class "Default")
      (node (ref "U501") (pin "N22") (pinfunction "IO_L15P_T2_DQS_15_N22") (pintype "bidirectional+no_connect"))
    )
    (net (code "121") (name "unconnected-(U501C-IO_L16N_T2_A27_15-PadL18)") (class "Default")
      (node (ref "U501") (pin "L18") (pinfunction "IO_L16N_T2_A27_15_L18") (pintype "bidirectional+no_connect"))
    )
    (net (code "122") (name "unconnected-(U501C-IO_L16P_T2_A28_15-PadM18)") (class "Default")
      (node (ref "U501") (pin "M18") (pinfunction "IO_L16P_T2_A28_15_M18") (pintype "bidirectional+no_connect"))
    )
    (net (code "123") (name "unconnected-(U501C-IO_L17N_T2_A25_15-PadN19)") (class "Default")
      (node (ref "U501") (pin "N19") (pinfunction "IO_L17N_T2_A25_15_N19") (pintype "bidirectional+no_connect"))
    )
    (net (code "124") (name "unconnected-(U501C-IO_L17P_T2_A26_15-PadN18)") (class "Default")
      (node (ref "U501") (pin "N18") (pinfunction "IO_L17P_T2_A26_15_N18") (pintype "bidirectional+no_connect"))
    )
    (net (code "125") (name "unconnected-(U501C-IO_L18N_T2_A23_15-PadM20)") (class "Default")
      (node (ref "U501") (pin "M20") (pinfunction "IO_L18N_T2_A23_15_M20") (pintype "bidirectional+no_connect"))
    )
    (net (code "126") (name "unconnected-(U501C-IO_L18P_T2_A24_15-PadN20)") (class "Default")
      (node (ref "U501") (pin "N20") (pinfunction "IO_L18P_T2_A24_15_N20") (pintype "bidirectional+no_connect"))
    )
    (net (code "127") (name "unconnected-(U501C-IO_L19N_T3_A21_VREF_15-PadK14)") (class "Default")
      (node (ref "U501") (pin "K14") (pinfunction "IO_L19N_T3_A21_VREF_15_K14") (pintype "bidirectional+no_connect"))
    )
    (net (code "128") (name "unconnected-(U501C-IO_L19P_T3_A22_15-PadK13)") (class "Default")
      (node (ref "U501") (pin "K13") (pinfunction "IO_L19P_T3_A22_15_K13") (pintype "bidirectional+no_connect"))
    )
    (net (code "129") (name "unconnected-(U501C-IO_L20N_T3_A19_15-PadL13)") (class "Default")
      (node (ref "U501") (pin "L13") (pinfunction "IO_L20N_T3_A19_15_L13") (pintype "bidirectional+no_connect"))
    )
    (net (code "130") (name "unconnected-(U501C-IO_L20P_T3_A20_15-PadM13)") (class "Default")
      (node (ref "U501") (pin "M13") (pinfunction "IO_L20P_T3_A20_15_M13") (pintype "bidirectional+no_connect"))
    )
    (net (code "131") (name "unconnected-(U501C-IO_L21N_T3_DQS_A18_15-PadJ17)") (class "Default")
      (node (ref "U501") (pin "J17") (pinfunction "IO_L21N_T3_DQS_A18_15_J17") (pintype "bidirectional+no_connect"))
    )
    (net (code "132") (name "unconnected-(U501C-IO_L21P_T3_DQS_15-PadK17)") (class "Default")
      (node (ref "U501") (pin "K17") (pinfunction "IO_L21P_T3_DQS_15_K17") (pintype "bidirectional+no_connect"))
    )
    (net (code "133") (name "unconnected-(U501C-IO_L22N_T3_A16_15-PadL15)") (class "Default")
      (node (ref "U501") (pin "L15") (pinfunction "IO_L22N_T3_A16_15_L15") (pintype "bidirectional+no_connect"))
    )
    (net (code "134") (name "unconnected-(U501C-IO_L22P_T3_A17_15-PadL14)") (class "Default")
      (node (ref "U501") (pin "L14") (pinfunction "IO_L22P_T3_A17_15_L14") (pintype "bidirectional+no_connect"))
    )
    (net (code "135") (name "unconnected-(U501C-IO_L23N_T3_FWE_B_15-PadK16)") (class "Default")
      (node (ref "U501") (pin "K16") (pinfunction "IO_L23N_T3_FWE_B_15_K16") (pintype "bidirectional+no_connect"))
    )
    (net (code "136") (name "unconnected-(U501C-IO_L23P_T3_FOE_B_15-PadL16)") (class "Default")
      (node (ref "U501") (pin "L16") (pinfunction "IO_L23P_T3_FOE_B_15_L16") (pintype "bidirectional+no_connect"))
    )
    (net (code "137") (name "unconnected-(U501C-IO_L24N_T3_RS0_15-PadM16)") (class "Default")
      (node (ref "U501") (pin "M16") (pinfunction "IO_L24N_T3_RS0_15_M16") (pintype "bidirectional+no_connect"))
    )
    (net (code "138") (name "unconnected-(U501C-IO_L24P_T3_RS1_15-PadM15)") (class "Default")
      (node (ref "U501") (pin "M15") (pinfunction "IO_L24P_T3_RS1_15_M15") (pintype "bidirectional+no_connect"))
    )
    (net (code "139") (name "unconnected-(U501D-IO_0_16-PadF15)") (class "Default")
      (node (ref "U501") (pin "F15") (pinfunction "IO_0_16_F15") (pintype "bidirectional+no_connect"))
    )
    (net (code "140") (name "unconnected-(U501D-IO_25_16-PadF21)") (class "Default")
      (node (ref "U501") (pin "F21") (pinfunction "IO_25_16_F21") (pintype "bidirectional+no_connect"))
    )
    (net (code "141") (name "unconnected-(U501D-IO_L1N_T0_16-PadF14)") (class "Default")
      (node (ref "U501") (pin "F14") (pinfunction "IO_L1N_T0_16_F14") (pintype "bidirectional+no_connect"))
    )
    (net (code "142") (name "unconnected-(U501D-IO_L1P_T0_16-PadF13)") (class "Default")
      (node (ref "U501") (pin "F13") (pinfunction "IO_L1P_T0_16_F13") (pintype "bidirectional+no_connect"))
    )
    (net (code "143") (name "unconnected-(U501D-IO_L2N_T0_16-PadE17)") (class "Default")
      (node (ref "U501") (pin "E17") (pinfunction "IO_L2N_T0_16_E17") (pintype "bidirectional+no_connect"))
    )
    (net (code "144") (name "unconnected-(U501D-IO_L2P_T0_16-PadF16)") (class "Default")
      (node (ref "U501") (pin "F16") (pinfunction "IO_L2P_T0_16_F16") (pintype "bidirectional+no_connect"))
    )
    (net (code "145") (name "unconnected-(U501D-IO_L3N_T0_DQS_16-PadC15)") (class "Default")
      (node (ref "U501") (pin "C15") (pinfunction "IO_L3N_T0_DQS_16_C15") (pintype "bidirectional+no_connect"))
    )
    (net (code "146") (name "unconnected-(U501D-IO_L3P_T0_DQS_16-PadC14)") (class "Default")
      (node (ref "U501") (pin "C14") (pinfunction "IO_L3P_T0_DQS_16_C14") (pintype "bidirectional+no_connect"))
    )
    (net (code "147") (name "unconnected-(U501D-IO_L4N_T0_16-PadE14)") (class "Default")
      (node (ref "U501") (pin "E14") (pinfunction "IO_L4N_T0_16_E14") (pintype "bidirectional+no_connect"))
    )
    (net (code "148") (name "unconnected-(U501D-IO_L4P_T0_16-PadE13)") (class "Default")
      (node (ref "U501") (pin "E13") (pinfunction "IO_L4P_T0_16_E13") (pintype "bidirectional+no_connect"))
    )
    (net (code "149") (name "unconnected-(U501D-IO_L5N_T0_16-PadD16)") (class "Default")
      (node (ref "U501") (pin "D16") (pinfunction "IO_L5N_T0_16_D16") (pintype "bidirectional+no_connect"))
    )
    (net (code "150") (name "unconnected-(U501D-IO_L5P_T0_16-PadE16)") (class "Default")
      (node (ref "U501") (pin "E16") (pinfunction "IO_L5P_T0_16_E16") (pintype "bidirectional+no_connect"))
    )
    (net (code "151") (name "unconnected-(U501D-IO_L6N_T0_VREF_16-PadD15)") (class "Default")
      (node (ref "U501") (pin "D15") (pinfunction "IO_L6N_T0_VREF_16_D15") (pintype "bidirectional+no_connect"))
    )
    (net (code "152") (name "unconnected-(U501D-IO_L6P_T0_16-PadD14)") (class "Default")
      (node (ref "U501") (pin "D14") (pinfunction "IO_L6P_T0_16_D14") (pintype "bidirectional+no_connect"))
    )
    (net (code "153") (name "unconnected-(U501D-IO_L7N_T1_16-PadB16)") (class "Default")
      (node (ref "U501") (pin "B16") (pinfunction "IO_L7N_T1_16_B16") (pintype "bidirectional+no_connect"))
    )
    (net (code "154") (name "unconnected-(U501D-IO_L7P_T1_16-PadB15)") (class "Default")
      (node (ref "U501") (pin "B15") (pinfunction "IO_L7P_T1_16_B15") (pintype "bidirectional+no_connect"))
    )
    (net (code "155") (name "unconnected-(U501D-IO_L8N_T1_16-PadB13)") (class "Default")
      (node (ref "U501") (pin "B13") (pinfunction "IO_L8N_T1_16_B13") (pintype "bidirectional+no_connect"))
    )
    (net (code "156") (name "unconnected-(U501D-IO_L8P_T1_16-PadC13)") (class "Default")
      (node (ref "U501") (pin "C13") (pinfunction "IO_L8P_T1_16_C13") (pintype "bidirectional+no_connect"))
    )
    (net (code "157") (name "unconnected-(U501D-IO_L9N_T1_DQS_16-PadA16)") (class "Default")
      (node (ref "U501") (pin "A16") (pinfunction "IO_L9N_T1_DQS_16_A16") (pintype "bidirectional+no_connect"))
    )
    (net (code "158") (name "unconnected-(U501D-IO_L9P_T1_DQS_16-PadA15)") (class "Default")
      (node (ref "U501") (pin "A15") (pinfunction "IO_L9P_T1_DQS_16_A15") (pintype "bidirectional+no_connect"))
    )
    (net (code "159") (name "unconnected-(U501D-IO_L10N_T1_16-PadA14)") (class "Default")
      (node (ref "U501") (pin "A14") (pinfunction "IO_L10N_T1_16_A14") (pintype "bidirectional+no_connect"))
    )
    (net (code "160") (name "unconnected-(U501D-IO_L10P_T1_16-PadA13)") (class "Default")
      (node (ref "U501") (pin "A13") (pinfunction "IO_L10P_T1_16_A13") (pintype "bidirectional+no_connect"))
    )
    (net (code "161") (name "unconnected-(U501D-IO_L11N_T1_SRCC_16-PadB18)") (class "Default")
      (node (ref "U501") (pin "B18") (pinfunction "IO_L11N_T1_SRCC_16_B18") (pintype "bidirectional+no_connect"))
    )
    (net (code "162") (name "unconnected-(U501D-IO_L11P_T1_SRCC_16-PadB17)") (class "Default")
      (node (ref "U501") (pin "B17") (pinfunction "IO_L11P_T1_SRCC_16_B17") (pintype "bidirectional+no_connect"))
    )
    (net (code "163") (name "unconnected-(U501D-IO_L12N_T1_MRCC_16-PadC17)") (class "Default")
      (node (ref "U501") (pin "C17") (pinfunction "IO_L12N_T1_MRCC_16_C17") (pintype "bidirectional+no_connect"))
    )
    (net (code "164") (name "unconnected-(U501D-IO_L12P_T1_MRCC_16-PadD17)") (class "Default")
      (node (ref "U501") (pin "D17") (pinfunction "IO_L12P_T1_MRCC_16_D17") (pintype "bidirectional+no_connect"))
    )
    (net (code "165") (name "unconnected-(U501D-IO_L13N_T2_MRCC_16-PadC19)") (class "Default")
      (node (ref "U501") (pin "C19") (pinfunction "IO_L13N_T2_MRCC_16_C19") (pintype "bidirectional+no_connect"))
    )
    (net (code "166") (name "unconnected-(U501D-IO_L13P_T2_MRCC_16-PadC18)") (class "Default")
      (node (ref "U501") (pin "C18") (pinfunction "IO_L13P_T2_MRCC_16_C18") (pintype "bidirectional+no_connect"))
    )
    (net (code "167") (name "unconnected-(U501D-IO_L14N_T2_SRCC_16-PadD19)") (class "Default")
      (node (ref "U501") (pin "D19") (pinfunction "IO_L14N_T2_SRCC_16_D19") (pintype "bidirectional+no_connect"))
    )
    (net (code "168") (name "unconnected-(U501D-IO_L14P_T2_SRCC_16-PadE19)") (class "Default")
      (node (ref "U501") (pin "E19") (pinfunction "IO_L14P_T2_SRCC_16_E19") (pintype "bidirectional+no_connect"))
    )
    (net (code "169") (name "unconnected-(U501D-IO_L15N_T2_DQS_16-PadE18)") (class "Default")
      (node (ref "U501") (pin "E18") (pinfunction "IO_L15N_T2_DQS_16_E18") (pintype "bidirectional+no_connect"))
    )
    (net (code "170") (name "unconnected-(U501D-IO_L15P_T2_DQS_16-PadF18)") (class "Default")
      (node (ref "U501") (pin "F18") (pinfunction "IO_L15P_T2_DQS_16_F18") (pintype "bidirectional+no_connect"))
    )
    (net (code "171") (name "unconnected-(U501D-IO_L16N_T2_16-PadA20)") (class "Default")
      (node (ref "U501") (pin "A20") (pinfunction "IO_L16N_T2_16_A20") (pintype "bidirectional+no_connect"))
    )
    (net (code "172") (name "unconnected-(U501D-IO_L16P_T2_16-PadB20)") (class "Default")
      (node (ref "U501") (pin "B20") (pinfunction "IO_L16P_T2_16_B20") (pintype "bidirectional+no_connect"))
    )
    (net (code "173") (name "unconnected-(U501D-IO_L17N_T2_16-PadA19)") (class "Default")
      (node (ref "U501") (pin "A19") (pinfunction "IO_L17N_T2_16_A19") (pintype "bidirectional+no_connect"))
    )
    (net (code "174") (name "unconnected-(U501D-IO_L17P_T2_16-PadA18)") (class "Default")
      (node (ref "U501") (pin "A18") (pinfunction "IO_L17P_T2_16_A18") (pintype "bidirectional+no_connect"))
    )
    (net (code "175") (name "unconnected-(U501D-IO_L18N_T2_16-PadF20)") (class "Default")
      (node (ref "U501") (pin "F20") (pinfunction "IO_L18N_T2_16_F20") (pintype "bidirectional+no_connect"))
    )
    (net (code "176") (name "unconnected-(U501D-IO_L18P_T2_16-PadF19)") (class "Default")
      (node (ref "U501") (pin "F19") (pinfunction "IO_L18P_T2_16_F19") (pintype "bidirectional+no_connect"))
    )
    (net (code "177") (name "unconnected-(U501D-IO_L19N_T3_VREF_16-PadC20)") (class "Default")
      (node (ref "U501") (pin "C20") (pinfunction "IO_L19N_T3_VREF_16_C20") (pintype "bidirectional+no_connect"))
    )
    (net (code "178") (name "unconnected-(U501D-IO_L19P_T3_16-PadD20)") (class "Default")
      (node (ref "U501") (pin "D20") (pinfunction "IO_L19P_T3_16_D20") (pintype "bidirectional+no_connect"))
    )
    (net (code "179") (name "unconnected-(U501D-IO_L20N_T3_16-PadB22)") (class "Default")
      (node (ref "U501") (pin "B22") (pinfunction "IO_L20N_T3_16_B22") (pintype "bidirectional+no_connect"))
    )
    (net (code "180") (name "unconnected-(U501D-IO_L20P_T3_16-PadC22)") (class "Default")
      (node (ref "U501") (pin "C22") (pinfunction "IO_L20P_T3_16_C22") (pintype "bidirectional+no_connect"))
    )
    (net (code "181") (name "unconnected-(U501D-IO_L21N_T3_DQS_16-PadA21)") (class "Default")
      (node (ref "U501") (pin "A21") (pinfunction "IO_L21N_T3_DQS_16_A21") (pintype "bidirectional+no_connect"))
    )
    (net (code "182") (name "unconnected-(U501D-IO_L21P_T3_DQS_16-PadB21)") (class "Default")
      (node (ref "U501") (pin "B21") (pinfunction "IO_L21P_T3_DQS_16_B21") (pintype "bidirectional+no_connect"))
    )
    (net (code "183") (name "unconnected-(U501D-IO_L22N_T3_16-PadD22)") (class "Default")
      (node (ref "U501") (pin "D22") (pinfunction "IO_L22N_T3_16_D22") (pintype "bidirectional+no_connect"))
    )
    (net (code "184") (name "unconnected-(U501D-IO_L22P_T3_16-PadE22)") (class "Default")
      (node (ref "U501") (pin "E22") (pinfunction "IO_L22P_T3_16_E22") (pintype "bidirectional+no_connect"))
    )
    (net (code "185") (name "unconnected-(U501D-IO_L23N_T3_16-PadD21)") (class "Default")
      (node (ref "U501") (pin "D21") (pinfunction "IO_L23N_T3_16_D21") (pintype "bidirectional+no_connect"))
    )
    (net (code "186") (name "unconnected-(U501D-IO_L23P_T3_16-PadE21)") (class "Default")
      (node (ref "U501") (pin "E21") (pinfunction "IO_L23P_T3_16_E21") (pintype "bidirectional+no_connect"))
    )
    (net (code "187") (name "unconnected-(U501D-IO_L24N_T3_16-PadG22)") (class "Default")
      (node (ref "U501") (pin "G22") (pinfunction "IO_L24N_T3_16_G22") (pintype "bidirectional+no_connect"))
    )
    (net (code "188") (name "unconnected-(U501D-IO_L24P_T3_16-PadG21)") (class "Default")
      (node (ref "U501") (pin "G21") (pinfunction "IO_L24P_T3_16_G21") (pintype "bidirectional+no_connect"))
    )
  )
)
